# Sheet1.net
KiCad netlist of a schematic drawn in Altium Designer
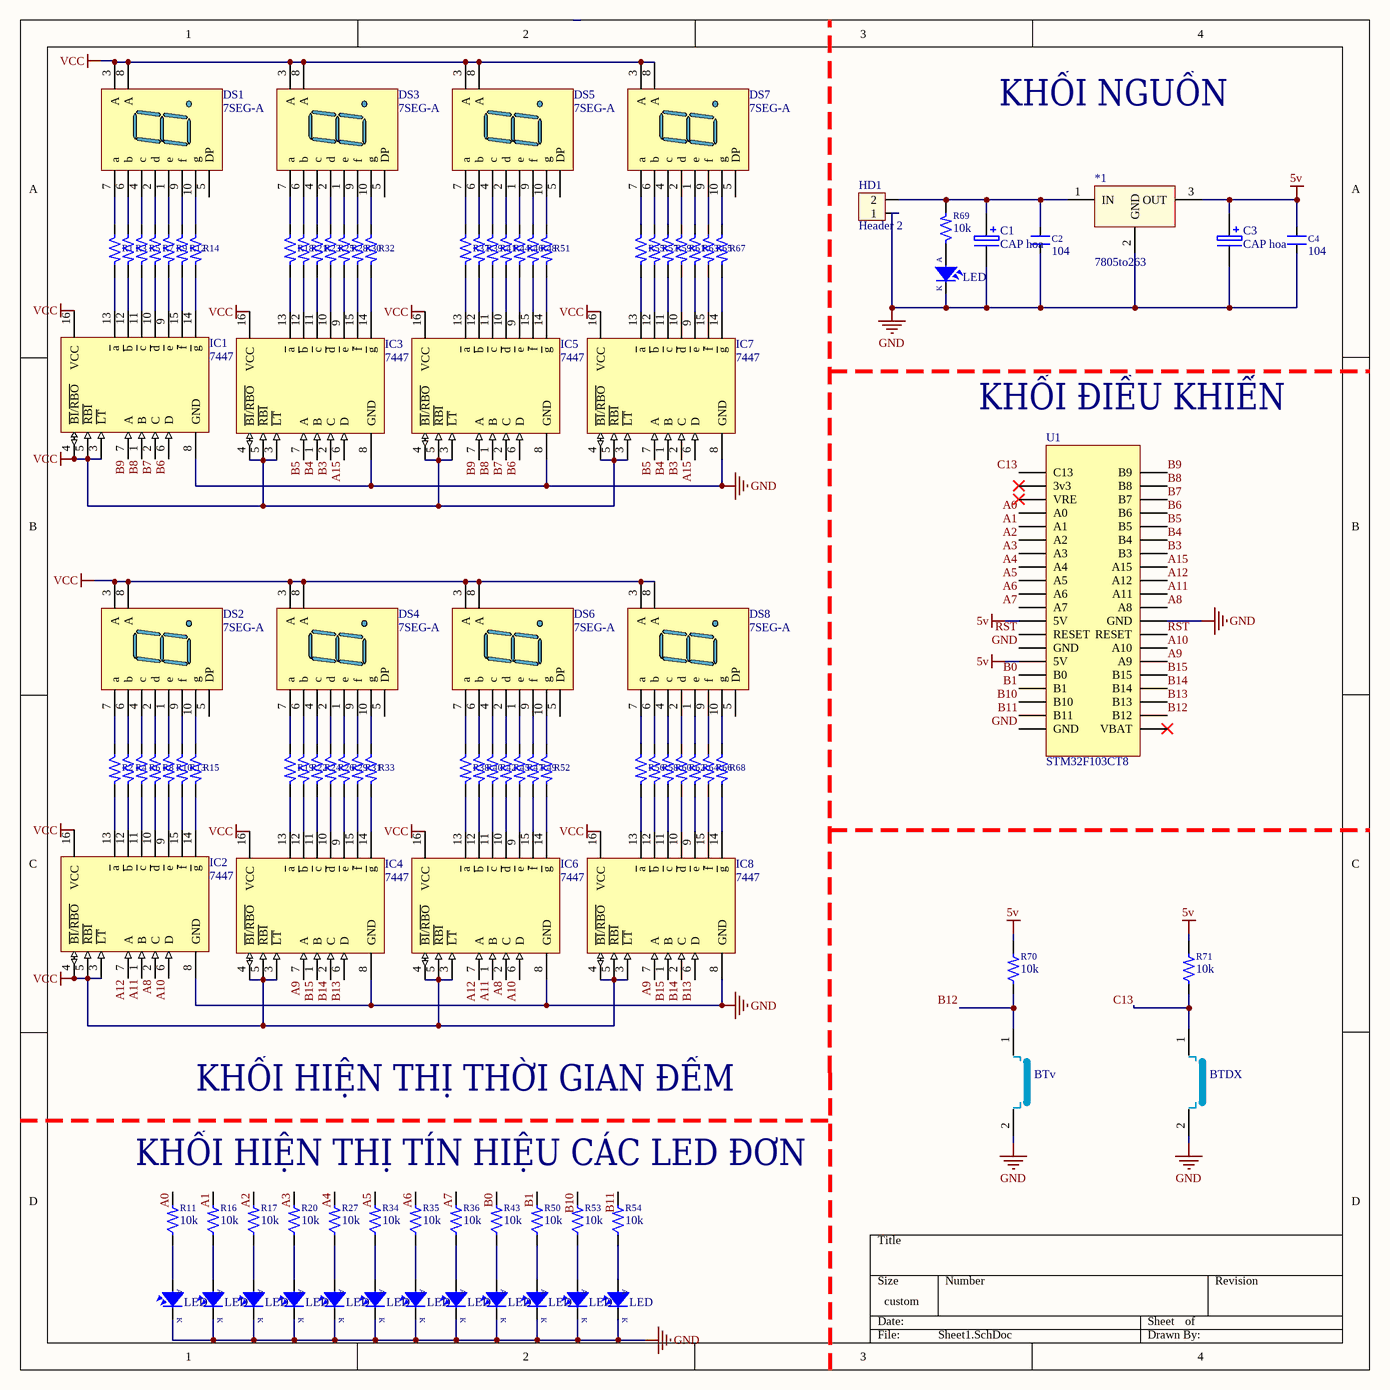
[diagram p0: Sheet1.SchDoc]

(export (version "E")
  (design (tool "Eeschema 10.0.6"))
  (components
    (comp (ref "*1") (value "7805to263") (footprint "7805") (libsource (lib "lananh_lib") (part "7805to263")))
    (comp (ref "BT1") (value "BTv") (footprint "SW4") (libsource (lib "CDT_Library") (part "BUTTON")))
    (comp (ref "BT2") (value "BTDX") (footprint "SW4") (libsource (lib "CDT_Library") (part "BUTTON")))
    (comp (ref "C1")
      (value "CAP hoa")
      (footprint "CP1/2")
      (description "Cap")
      (libsource (lib "CDT_Library") (part "CAP hoa"))
    )
    (comp (ref "C2")
      (value "104")
      (footprint "SM-CAP-0805")
      (fields (field (name "DESIGNED BY") "VanDungEvn"))
      (libsource (lib "CDT_Library") (part "CAP SMD"))
    )
    (comp (ref "C3")
      (value "CAP hoa")
      (footprint "CP1/2")
      (description "Cap")
      (libsource (lib "CDT_Library") (part "CAP hoa"))
    )
    (comp (ref "C4")
      (value "104")
      (footprint "SM-CAP-0805")
      (fields (field (name "DESIGNED BY") "VanDungEvn"))
      (libsource (lib "CDT_Library") (part "CAP SMD"))
    )
    (comp (ref "DS1")
      (value "7SEG-A")
      (footprint "LED7SEG")
      (description "14.2 mm General Purpose Blue 7-Segment Display: CA, RH DP, Gray Surface")
      (fields (field (name "PUBLISHER") "Altium Limited"))
      (libsource (lib "CDT_Library") (part "LED 7SEG-A"))
    )
    (comp (ref "DS2")
      (value "7SEG-A")
      (footprint "LED7SEG")
      (description "14.2 mm General Purpose Blue 7-Segment Display: CA, RH DP, Gray Surface")
      (fields (field (name "PUBLISHER") "Altium Limited"))
      (libsource (lib "CDT_Library") (part "LED 7SEG-A"))
    )
    (comp (ref "DS3")
      (value "7SEG-A")
      (footprint "LED7SEG")
      (description "14.2 mm General Purpose Blue 7-Segment Display: CA, RH DP, Gray Surface")
      (fields (field (name "PUBLISHER") "Altium Limited"))
      (libsource (lib "CDT_Library") (part "LED 7SEG-A"))
    )
    (comp (ref "DS4")
      (value "7SEG-A")
      (footprint "LED7SEG")
      (description "14.2 mm General Purpose Blue 7-Segment Display: CA, RH DP, Gray Surface")
      (fields (field (name "PUBLISHER") "Altium Limited"))
      (libsource (lib "CDT_Library") (part "LED 7SEG-A"))
    )
    (comp (ref "DS5")
      (value "7SEG-A")
      (footprint "LED7SEG")
      (description "14.2 mm General Purpose Blue 7-Segment Display: CA, RH DP, Gray Surface")
      (fields (field (name "PUBLISHER") "Altium Limited"))
      (libsource (lib "CDT_Library") (part "LED 7SEG-A"))
    )
    (comp (ref "DS6")
      (value "7SEG-A")
      (footprint "LED7SEG")
      (description "14.2 mm General Purpose Blue 7-Segment Display: CA, RH DP, Gray Surface")
      (fields (field (name "PUBLISHER") "Altium Limited"))
      (libsource (lib "CDT_Library") (part "LED 7SEG-A"))
    )
    (comp (ref "DS7")
      (value "7SEG-A")
      (footprint "LED7SEG")
      (description "14.2 mm General Purpose Blue 7-Segment Display: CA, RH DP, Gray Surface")
      (fields (field (name "PUBLISHER") "Altium Limited"))
      (libsource (lib "CDT_Library") (part "LED 7SEG-A"))
    )
    (comp (ref "DS8")
      (value "7SEG-A")
      (footprint "LED7SEG")
      (description "14.2 mm General Purpose Blue 7-Segment Display: CA, RH DP, Gray Surface")
      (fields (field (name "PUBLISHER") "Altium Limited"))
      (libsource (lib "CDT_Library") (part "LED 7SEG-A"))
    )
    (comp (ref "HD1")
      (value "Header 2")
      (footprint "HED2")
      (description "Header 2 (Green)")
      (libsource (lib "CDT_Library") (part "Header 2"))
    )
    (comp (ref "IC1")
      (value "7447")
      (footprint "ic74ls47")
      (description "BCD to 7-Segment Decoder/Driver")
      (libsource (lib "CDT_Library") (part "7447"))
    )
    (comp (ref "IC2")
      (value "7447")
      (footprint "ic74ls47")
      (description "BCD to 7-Segment Decoder/Driver")
      (libsource (lib "CDT_Library") (part "7447"))
    )
    (comp (ref "IC3")
      (value "7447")
      (footprint "ic74ls47")
      (description "BCD to 7-Segment Decoder/Driver")
      (libsource (lib "CDT_Library") (part "7447"))
    )
    (comp (ref "IC4")
      (value "7447")
      (footprint "ic74ls47")
      (description "BCD to 7-Segment Decoder/Driver")
      (libsource (lib "CDT_Library") (part "7447"))
    )
    (comp (ref "IC5")
      (value "7447")
      (footprint "ic74ls47")
      (description "BCD to 7-Segment Decoder/Driver")
      (libsource (lib "CDT_Library") (part "7447"))
    )
    (comp (ref "IC6")
      (value "7447")
      (footprint "ic74ls47")
      (description "BCD to 7-Segment Decoder/Driver")
      (libsource (lib "CDT_Library") (part "7447"))
    )
    (comp (ref "IC7")
      (value "7447")
      (footprint "ic74ls47")
      (description "BCD to 7-Segment Decoder/Driver")
      (libsource (lib "CDT_Library") (part "7447"))
    )
    (comp (ref "IC8")
      (value "7447")
      (footprint "ic74ls47")
      (description "BCD to 7-Segment Decoder/Driver")
      (libsource (lib "CDT_Library") (part "7447"))
    )
    (comp (ref "LED1")
      (value "LED")
      (footprint "LED-3")
      (description "LED Single colour Green and Red")
      (libsource (lib "CDT_Library") (part "LED"))
    )
    (comp (ref "LED2")
      (value "LED")
      (footprint "LED-3")
      (description "LED Single colour Green and Red")
      (libsource (lib "CDT_Library") (part "LED"))
    )
    (comp (ref "LED3")
      (value "LED")
      (footprint "LED-3")
      (description "LED Single colour Green and Red")
      (libsource (lib "CDT_Library") (part "LED"))
    )
    (comp (ref "LED4")
      (value "LED")
      (footprint "LED-3")
      (description "LED Single colour Green and Red")
      (libsource (lib "CDT_Library") (part "LED"))
    )
    (comp (ref "LED5")
      (value "LED")
      (footprint "LED-3")
      (description "LED Single colour Green and Red")
      (libsource (lib "CDT_Library") (part "LED"))
    )
    (comp (ref "LED6")
      (value "LED")
      (footprint "LED-3")
      (description "LED Single colour Green and Red")
      (libsource (lib "CDT_Library") (part "LED"))
    )
    (comp (ref "LED7")
      (value "LED")
      (footprint "LED-3")
      (description "LED Single colour Green and Red")
      (libsource (lib "CDT_Library") (part "LED"))
    )
    (comp (ref "LED8")
      (value "LED")
      (footprint "LED-3")
      (description "LED Single colour Green and Red")
      (libsource (lib "CDT_Library") (part "LED"))
    )
    (comp (ref "LED9")
      (value "LED")
      (footprint "LED-3")
      (description "LED Single colour Green and Red")
      (libsource (lib "CDT_Library") (part "LED"))
    )
    (comp (ref "LED10")
      (value "LED")
      (footprint "LED-3")
      (description "LED Single colour Green and Red")
      (libsource (lib "CDT_Library") (part "LED"))
    )
    (comp (ref "LED11")
      (value "LED")
      (footprint "LED-3")
      (description "LED Single colour Green and Red")
      (libsource (lib "CDT_Library") (part "LED"))
    )
    (comp (ref "LED12")
      (value "LED")
      (footprint "LED-3")
      (description "LED Single colour Green and Red")
      (libsource (lib "CDT_Library") (part "LED"))
    )
    (comp (ref "LED13")
      (value "LED")
      (footprint "LED-3")
      (description "LED Single colour Green and Red")
      (libsource (lib "CDT_Library") (part "LED"))
    )
    (comp (ref "R1")
      (value "10k")
      (footprint "Resistor SMD0603")
      (description "Res")
      (libsource (lib "CDT_Library") (part "Res SMD"))
    )
    (comp (ref "R2")
      (value "10k")
      (footprint "Resistor SMD0603")
      (description "Res")
      (libsource (lib "CDT_Library") (part "Res SMD"))
    )
    (comp (ref "R3")
      (value "10k")
      (footprint "Resistor SMD0603")
      (description "Res")
      (libsource (lib "CDT_Library") (part "Res SMD"))
    )
    (comp (ref "R4")
      (value "10k")
      (footprint "Resistor SMD0603")
      (description "Res")
      (libsource (lib "CDT_Library") (part "Res SMD"))
    )
    (comp (ref "R5")
      (value "10k")
      (footprint "Resistor SMD0603")
      (description "Res")
      (libsource (lib "CDT_Library") (part "Res SMD"))
    )
    (comp (ref "R6")
      (value "10k")
      (footprint "Resistor SMD0603")
      (description "Res")
      (libsource (lib "CDT_Library") (part "Res SMD"))
    )
    (comp (ref "R7")
      (value "10k")
      (footprint "Resistor SMD0603")
      (description "Res")
      (libsource (lib "CDT_Library") (part "Res SMD"))
    )
    (comp (ref "R8")
      (value "10k")
      (footprint "Resistor SMD0603")
      (description "Res")
      (libsource (lib "CDT_Library") (part "Res SMD"))
    )
    (comp (ref "R9")
      (value "10k")
      (footprint "Resistor SMD0603")
      (description "Res")
      (libsource (lib "CDT_Library") (part "Res SMD"))
    )
    (comp (ref "R10")
      (value "10k")
      (footprint "Resistor SMD0603")
      (description "Res")
      (libsource (lib "CDT_Library") (part "Res SMD"))
    )
    (comp (ref "R11")
      (value "10k")
      (footprint "Resistor SMD0603")
      (description "Res")
      (libsource (lib "CDT_Library") (part "Res SMD"))
    )
    (comp (ref "R12")
      (value "10k")
      (footprint "Resistor SMD0603")
      (description "Res")
      (libsource (lib "CDT_Library") (part "Res SMD"))
    )
    (comp (ref "R13")
      (value "10k")
      (footprint "Resistor SMD0603")
      (description "Res")
      (libsource (lib "CDT_Library") (part "Res SMD"))
    )
    (comp (ref "R14")
      (value "10k")
      (footprint "Resistor SMD0603")
      (description "Res")
      (libsource (lib "CDT_Library") (part "Res SMD"))
    )
    (comp (ref "R15")
      (value "10k")
      (footprint "Resistor SMD0603")
      (description "Res")
      (libsource (lib "CDT_Library") (part "Res SMD"))
    )
    (comp (ref "R16")
      (value "10k")
      (footprint "Resistor SMD0603")
      (description "Res")
      (libsource (lib "CDT_Library") (part "Res SMD"))
    )
    (comp (ref "R17")
      (value "10k")
      (footprint "Resistor SMD0603")
      (description "Res")
      (libsource (lib "CDT_Library") (part "Res SMD"))
    )
    (comp (ref "R18")
      (value "10k")
      (footprint "Resistor SMD0603")
      (description "Res")
      (libsource (lib "CDT_Library") (part "Res SMD"))
    )
    (comp (ref "R19")
      (value "10k")
      (footprint "Resistor SMD0603")
      (description "Res")
      (libsource (lib "CDT_Library") (part "Res SMD"))
    )
    (comp (ref "R20")
      (value "10k")
      (footprint "Resistor SMD0603")
      (description "Res")
      (libsource (lib "CDT_Library") (part "Res SMD"))
    )
    (comp (ref "R21")
      (value "10k")
      (footprint "Resistor SMD0603")
      (description "Res")
      (libsource (lib "CDT_Library") (part "Res SMD"))
    )
    (comp (ref "R22")
      (value "10k")
      (footprint "Resistor SMD0603")
      (description "Res")
      (libsource (lib "CDT_Library") (part "Res SMD"))
    )
    (comp (ref "R23")
      (value "10k")
      (footprint "Resistor SMD0603")
      (description "Res")
      (libsource (lib "CDT_Library") (part "Res SMD"))
    )
    (comp (ref "R24")
      (value "10k")
      (footprint "Resistor SMD0603")
      (description "Res")
      (libsource (lib "CDT_Library") (part "Res SMD"))
    )
    (comp (ref "R25")
      (value "10k")
      (footprint "Resistor SMD0603")
      (description "Res")
      (libsource (lib "CDT_Library") (part "Res SMD"))
    )
    (comp (ref "R26")
      (value "10k")
      (footprint "Resistor SMD0603")
      (description "Res")
      (libsource (lib "CDT_Library") (part "Res SMD"))
    )
    (comp (ref "R27")
      (value "10k")
      (footprint "Resistor SMD0603")
      (description "Res")
      (libsource (lib "CDT_Library") (part "Res SMD"))
    )
    (comp (ref "R28")
      (value "10k")
      (footprint "Resistor SMD0603")
      (description "Res")
      (libsource (lib "CDT_Library") (part "Res SMD"))
    )
    (comp (ref "R29")
      (value "10k")
      (footprint "Resistor SMD0603")
      (description "Res")
      (libsource (lib "CDT_Library") (part "Res SMD"))
    )
    (comp (ref "R30")
      (value "10k")
      (footprint "Resistor SMD0603")
      (description "Res")
      (libsource (lib "CDT_Library") (part "Res SMD"))
    )
    (comp (ref "R31")
      (value "10k")
      (footprint "Resistor SMD0603")
      (description "Res")
      (libsource (lib "CDT_Library") (part "Res SMD"))
    )
    (comp (ref "R32")
      (value "10k")
      (footprint "Resistor SMD0603")
      (description "Res")
      (libsource (lib "CDT_Library") (part "Res SMD"))
    )
    (comp (ref "R33")
      (value "10k")
      (footprint "Resistor SMD0603")
      (description "Res")
      (libsource (lib "CDT_Library") (part "Res SMD"))
    )
    (comp (ref "R34")
      (value "10k")
      (footprint "Resistor SMD0603")
      (description "Res")
      (libsource (lib "CDT_Library") (part "Res SMD"))
    )
    (comp (ref "R35")
      (value "10k")
      (footprint "Resistor SMD0603")
      (description "Res")
      (libsource (lib "CDT_Library") (part "Res SMD"))
    )
    (comp (ref "R36")
      (value "10k")
      (footprint "Resistor SMD0603")
      (description "Res")
      (libsource (lib "CDT_Library") (part "Res SMD"))
    )
    (comp (ref "R37")
      (value "10k")
      (footprint "Resistor SMD0603")
      (description "Res")
      (libsource (lib "CDT_Library") (part "Res SMD"))
    )
    (comp (ref "R38")
      (value "10k")
      (footprint "Resistor SMD0603")
      (description "Res")
      (libsource (lib "CDT_Library") (part "Res SMD"))
    )
    (comp (ref "R39")
      (value "10k")
      (footprint "Resistor SMD0603")
      (description "Res")
      (libsource (lib "CDT_Library") (part "Res SMD"))
    )
    (comp (ref "R40")
      (value "10k")
      (footprint "Resistor SMD0603")
      (description "Res")
      (libsource (lib "CDT_Library") (part "Res SMD"))
    )
    (comp (ref "R41")
      (value "10k")
      (footprint "Resistor SMD0603")
      (description "Res")
      (libsource (lib "CDT_Library") (part "Res SMD"))
    )
    (comp (ref "R42")
      (value "10k")
      (footprint "Resistor SMD0603")
      (description "Res")
      (libsource (lib "CDT_Library") (part "Res SMD"))
    )
    (comp (ref "R43")
      (value "10k")
      (footprint "Resistor SMD0603")
      (description "Res")
      (libsource (lib "CDT_Library") (part "Res SMD"))
    )
    (comp (ref "R44")
      (value "10k")
      (footprint "Resistor SMD0603")
      (description "Res")
      (libsource (lib "CDT_Library") (part "Res SMD"))
    )
    (comp (ref "R45")
      (value "10k")
      (footprint "Resistor SMD0603")
      (description "Res")
      (libsource (lib "CDT_Library") (part "Res SMD"))
    )
    (comp (ref "R46")
      (value "10k")
      (footprint "Resistor SMD0603")
      (description "Res")
      (libsource (lib "CDT_Library") (part "Res SMD"))
    )
    (comp (ref "R47")
      (value "10k")
      (footprint "Resistor SMD0603")
      (description "Res")
      (libsource (lib "CDT_Library") (part "Res SMD"))
    )
    (comp (ref "R48")
      (value "10k")
      (footprint "Resistor SMD0603")
      (description "Res")
      (libsource (lib "CDT_Library") (part "Res SMD"))
    )
    (comp (ref "R49")
      (value "10k")
      (footprint "Resistor SMD0603")
      (description "Res")
      (libsource (lib "CDT_Library") (part "Res SMD"))
    )
    (comp (ref "R50")
      (value "10k")
      (footprint "Resistor SMD0603")
      (description "Res")
      (libsource (lib "CDT_Library") (part "Res SMD"))
    )
    (comp (ref "R51")
      (value "10k")
      (footprint "Resistor SMD0603")
      (description "Res")
      (libsource (lib "CDT_Library") (part "Res SMD"))
    )
    (comp (ref "R52")
      (value "10k")
      (footprint "Resistor SMD0603")
      (description "Res")
      (libsource (lib "CDT_Library") (part "Res SMD"))
    )
    (comp (ref "R53")
      (value "10k")
      (footprint "Resistor SMD0603")
      (description "Res")
      (libsource (lib "CDT_Library") (part "Res SMD"))
    )
    (comp (ref "R54")
      (value "10k")
      (footprint "Resistor SMD0603")
      (description "Res")
      (libsource (lib "CDT_Library") (part "Res SMD"))
    )
    (comp (ref "R55")
      (value "10k")
      (footprint "Resistor SMD0603")
      (description "Res")
      (libsource (lib "CDT_Library") (part "Res SMD"))
    )
    (comp (ref "R56")
      (value "10k")
      (footprint "Resistor SMD0603")
      (description "Res")
      (libsource (lib "CDT_Library") (part "Res SMD"))
    )
    (comp (ref "R57")
      (value "10k")
      (footprint "Resistor SMD0603")
      (description "Res")
      (libsource (lib "CDT_Library") (part "Res SMD"))
    )
    (comp (ref "R58")
      (value "10k")
      (footprint "Resistor SMD0603")
      (description "Res")
      (libsource (lib "CDT_Library") (part "Res SMD"))
    )
    (comp (ref "R59")
      (value "10k")
      (footprint "Resistor SMD0603")
      (description "Res")
      (libsource (lib "CDT_Library") (part "Res SMD"))
    )
    (comp (ref "R60")
      (value "10k")
      (footprint "Resistor SMD0603")
      (description "Res")
      (libsource (lib "CDT_Library") (part "Res SMD"))
    )
    (comp (ref "R61")
      (value "10k")
      (footprint "Resistor SMD0603")
      (description "Res")
      (libsource (lib "CDT_Library") (part "Res SMD"))
    )
    (comp (ref "R62")
      (value "10k")
      (footprint "Resistor SMD0603")
      (description "Res")
      (libsource (lib "CDT_Library") (part "Res SMD"))
    )
    (comp (ref "R63")
      (value "10k")
      (footprint "Resistor SMD0603")
      (description "Res")
      (libsource (lib "CDT_Library") (part "Res SMD"))
    )
    (comp (ref "R64")
      (value "10k")
      (footprint "Resistor SMD0603")
      (description "Res")
      (libsource (lib "CDT_Library") (part "Res SMD"))
    )
    (comp (ref "R65")
      (value "10k")
      (footprint "Resistor SMD0603")
      (description "Res")
      (libsource (lib "CDT_Library") (part "Res SMD"))
    )
    (comp (ref "R66")
      (value "10k")
      (footprint "Resistor SMD0603")
      (description "Res")
      (libsource (lib "CDT_Library") (part "Res SMD"))
    )
    (comp (ref "R67")
      (value "10k")
      (footprint "Resistor SMD0603")
      (description "Res")
      (libsource (lib "CDT_Library") (part "Res SMD"))
    )
    (comp (ref "R68")
      (value "10k")
      (footprint "Resistor SMD0603")
      (description "Res")
      (libsource (lib "CDT_Library") (part "Res SMD"))
    )
    (comp (ref "R69")
      (value "10k")
      (footprint "Resistor SMD0603")
      (description "Res")
      (libsource (lib "CDT_Library") (part "Res SMD"))
    )
    (comp (ref "R70")
      (value "10k")
      (footprint "Resistor SMD0603")
      (description "Res")
      (libsource (lib "CDT_Library") (part "Res SMD"))
    )
    (comp (ref "R71")
      (value "10k")
      (footprint "Resistor SMD0603")
      (description "Res")
      (libsource (lib "CDT_Library") (part "Res SMD"))
    )
    (comp (ref "U1")
      (value "STM32F103CT8")
      (footprint "STM32F103CT6")
      (libsource (lib "Stm32f103ct6") (part "STM32F103CT8"))
    )
  )
  (nets
    (net (code "1") (name "/A0") (class "Default")
      (node (ref "R11") (pin "2") (pinfunction "2_2") (pintype "passive"))
      (node (ref "U1") (pin "4") (pinfunction "A0_4") (pintype "passive"))
    )
    (net (code "2") (name "/A1") (class "Default")
      (node (ref "R16") (pin "2") (pinfunction "2_2") (pintype "passive"))
      (node (ref "U1") (pin "5") (pinfunction "A1_5") (pintype "passive"))
    )
    (net (code "3") (name "/A2") (class "Default")
      (node (ref "R17") (pin "2") (pinfunction "2_2") (pintype "passive"))
      (node (ref "U1") (pin "6") (pinfunction "A2_6") (pintype "passive"))
    )
    (net (code "4") (name "/A3") (class "Default")
      (node (ref "R20") (pin "2") (pinfunction "2_2") (pintype "passive"))
      (node (ref "U1") (pin "7") (pinfunction "A3_7") (pintype "passive"))
    )
    (net (code "5") (name "/A4") (class "Default")
      (node (ref "R27") (pin "2") (pinfunction "2_2") (pintype "passive"))
      (node (ref "U1") (pin "8") (pinfunction "A4_8") (pintype "passive"))
    )
    (net (code "6") (name "/A5") (class "Default")
      (node (ref "R34") (pin "2") (pinfunction "2_2") (pintype "passive"))
      (node (ref "U1") (pin "9") (pinfunction "A5_9") (pintype "passive"))
    )
    (net (code "7") (name "/A6") (class "Default")
      (node (ref "R35") (pin "2") (pinfunction "2_2") (pintype "passive"))
      (node (ref "U1") (pin "10") (pinfunction "A6_10") (pintype "passive"))
    )
    (net (code "8") (name "/A7") (class "Default")
      (node (ref "R36") (pin "2") (pinfunction "2_2") (pintype "passive"))
      (node (ref "U1") (pin "11") (pinfunction "A7_11") (pintype "passive"))
    )
    (net (code "9") (name "/A8") (class "Default")
      (node (ref "IC2") (pin "2") (pinfunction "C_2") (pintype "input"))
      (node (ref "IC6") (pin "2") (pinfunction "C_2") (pintype "input"))
      (node (ref "U1") (pin "31") (pinfunction "A8_31") (pintype "passive"))
    )
    (net (code "10") (name "/A9") (class "Default")
      (node (ref "IC4") (pin "7") (pinfunction "A_7") (pintype "input"))
      (node (ref "IC8") (pin "7") (pinfunction "A_7") (pintype "input"))
      (node (ref "U1") (pin "35") (pinfunction "A9_35") (pintype "passive"))
    )
    (net (code "11") (name "/A10") (class "Default")
      (node (ref "IC2") (pin "6") (pinfunction "D_6") (pintype "input"))
      (node (ref "IC6") (pin "6") (pinfunction "D_6") (pintype "input"))
      (node (ref "U1") (pin "34") (pinfunction "A10_34") (pintype "passive"))
    )
    (net (code "12") (name "/A11") (class "Default")
      (node (ref "IC2") (pin "1") (pinfunction "B_1") (pintype "input"))
      (node (ref "IC6") (pin "1") (pinfunction "B_1") (pintype "input"))
      (node (ref "U1") (pin "30") (pinfunction "A11_30") (pintype "passive"))
    )
    (net (code "13") (name "/A12") (class "Default")
      (node (ref "IC2") (pin "7") (pinfunction "A_7") (pintype "input"))
      (node (ref "IC6") (pin "7") (pinfunction "A_7") (pintype "input"))
      (node (ref "U1") (pin "29") (pinfunction "A12_29") (pintype "passive"))
    )
    (net (code "14") (name "/A15") (class "Default")
      (node (ref "IC3") (pin "6") (pinfunction "D_6") (pintype "input"))
      (node (ref "IC7") (pin "6") (pinfunction "D_6") (pintype "input"))
      (node (ref "U1") (pin "28") (pinfunction "A15_28") (pintype "passive"))
    )
    (net (code "15") (name "/B0") (class "Default")
      (node (ref "R43") (pin "2") (pinfunction "2_2") (pintype "passive"))
      (node (ref "U1") (pin "16") (pinfunction "B0_16") (pintype "passive"))
    )
    (net (code "16") (name "/B1") (class "Default")
      (node (ref "R50") (pin "2") (pinfunction "2_2") (pintype "passive"))
      (node (ref "U1") (pin "17") (pinfunction "B1_17") (pintype "passive"))
    )
    (net (code "17") (name "/B3") (class "Default")
      (node (ref "IC3") (pin "2") (pinfunction "C_2") (pintype "input"))
      (node (ref "IC7") (pin "2") (pinfunction "C_2") (pintype "input"))
      (node (ref "U1") (pin "27") (pinfunction "B3_27") (pintype "passive"))
    )
    (net (code "18") (name "/B4") (class "Default")
      (node (ref "IC3") (pin "1") (pinfunction "B_1") (pintype "input"))
      (node (ref "IC7") (pin "1") (pinfunction "B_1") (pintype "input"))
      (node (ref "U1") (pin "26") (pinfunction "B4_26") (pintype "passive"))
    )
    (net (code "19") (name "/B5") (class "Default")
      (node (ref "IC3") (pin "7") (pinfunction "A_7") (pintype "input"))
      (node (ref "IC7") (pin "7") (pinfunction "A_7") (pintype "input"))
      (node (ref "U1") (pin "25") (pinfunction "B5_25") (pintype "passive"))
    )
    (net (code "20") (name "/B6") (class "Default")
      (node (ref "IC1") (pin "6") (pinfunction "D_6") (pintype "input"))
      (node (ref "IC5") (pin "6") (pinfunction "D_6") (pintype "input"))
      (node (ref "U1") (pin "24") (pinfunction "B6_24") (pintype "passive"))
    )
    (net (code "21") (name "/B7") (class "Default")
      (node (ref "IC1") (pin "2") (pinfunction "C_2") (pintype "input"))
      (node (ref "IC5") (pin "2") (pinfunction "C_2") (pintype "input"))
      (node (ref "U1") (pin "23") (pinfunction "B7_23") (pintype "power_in"))
    )
    (net (code "22") (name "/B8") (class "Default")
      (node (ref "IC1") (pin "1") (pinfunction "B_1") (pintype "input"))
      (node (ref "IC5") (pin "1") (pinfunction "B_1") (pintype "input"))
      (node (ref "U1") (pin "22") (pinfunction "B8_22") (pintype "passive"))
    )
    (net (code "23") (name "/B9") (class "Default")
      (node (ref "IC1") (pin "7") (pinfunction "A_7") (pintype "input"))
      (node (ref "IC5") (pin "7") (pinfunction "A_7") (pintype "input"))
      (node (ref "U1") (pin "21") (pinfunction "B9_21") (pintype "passive"))
    )
    (net (code "24") (name "/B10") (class "Default")
      (node (ref "R53") (pin "2") (pinfunction "2_2") (pintype "passive"))
      (node (ref "U1") (pin "18") (pinfunction "B10_18") (pintype "passive"))
    )
    (net (code "25") (name "/B11") (class "Default")
      (node (ref "R54") (pin "2") (pinfunction "2_2") (pintype "passive"))
      (node (ref "U1") (pin "19") (pinfunction "B11_19") (pintype "power_in"))
    )
    (net (code "26") (name "/B12") (class "Default")
      (node (ref "BT1") (pin "1") (pinfunction "1_1") (pintype "passive"))
      (node (ref "R70") (pin "1") (pinfunction "1_1") (pintype "passive"))
      (node (ref "U1") (pin "39") (pinfunction "B12_39") (pintype "passive"))
    )
    (net (code "27") (name "/B13") (class "Default")
      (node (ref "IC4") (pin "6") (pinfunction "D_6") (pintype "input"))
      (node (ref "IC8") (pin "6") (pinfunction "D_6") (pintype "input"))
      (node (ref "U1") (pin "38") (pinfunction "B13_38") (pintype "passive"))
    )
    (net (code "28") (name "/B14") (class "Default")
      (node (ref "IC4") (pin "2") (pinfunction "C_2") (pintype "input"))
      (node (ref "IC8") (pin "2") (pinfunction "C_2") (pintype "input"))
      (node (ref "U1") (pin "37") (pinfunction "B14_37") (pintype "passive"))
    )
    (net (code "29") (name "/B15") (class "Default")
      (node (ref "IC4") (pin "1") (pinfunction "B_1") (pintype "input"))
      (node (ref "IC8") (pin "1") (pinfunction "B_1") (pintype "input"))
      (node (ref "U1") (pin "36") (pinfunction "B15_36") (pintype "passive"))
    )
    (net (code "30") (name "/C13") (class "Default")
      (node (ref "BT2") (pin "1") (pinfunction "1_1") (pintype "passive"))
      (node (ref "R71") (pin "1") (pinfunction "1_1") (pintype "passive"))
      (node (ref "U1") (pin "1") (pinfunction "C13_1") (pintype "passive"))
    )
    (net (code "31") (name "/RST") (class "Default")
      (node (ref "U1") (pin "13") (pinfunction "RESET_13") (pintype "passive"))
      (node (ref "U1") (pin "33") (pinfunction "RESET_33") (pintype "passive"))
    )
    (net (code "32") (name "5v") (class "Default")
      (node (ref "*1") (pin "3") (pinfunction "OUT_3") (pintype "passive"))
      (node (ref "C3") (pin "1") (pintype "passive"))
      (node (ref "C4") (pin "2") (pinfunction "2_2") (pintype "passive"))
      (node (ref "R70") (pin "2") (pinfunction "2_2") (pintype "passive"))
      (node (ref "R71") (pin "2") (pinfunction "2_2") (pintype "passive"))
      (node (ref "U1") (pin "12") (pinfunction "5V_12") (pintype "power_in"))
      (node (ref "U1") (pin "15") (pinfunction "5V_15") (pintype "passive"))
    )
    (net (code "33") (name "GND") (class "Default")
      (node (ref "*1") (pin "2") (pinfunction "GND_2") (pintype "passive"))
      (node (ref "BT1") (pin "2") (pinfunction "2_2") (pintype "passive"))
      (node (ref "BT2") (pin "2") (pinfunction "2_2") (pintype "passive"))
      (node (ref "C1") (pin "2") (pintype "passive"))
      (node (ref "C2") (pin "1") (pinfunction "1_1") (pintype "passive"))
      (node (ref "C3") (pin "2") (pintype "passive"))
      (node (ref "C4") (pin "1") (pinfunction "1_1") (pintype "passive"))
      (node (ref "HD1") (pin "1") (pinfunction "1_1") (pintype "passive"))
      (node (ref "IC1") (pin "8") (pinfunction "GND_8") (pintype "power_in"))
      (node (ref "IC2") (pin "8") (pinfunction "GND_8") (pintype "power_in"))
      (node (ref "IC3") (pin "8") (pinfunction "GND_8") (pintype "power_in"))
      (node (ref "IC4") (pin "8") (pinfunction "GND_8") (pintype "power_in"))
      (node (ref "IC5") (pin "8") (pinfunction "GND_8") (pintype "power_in"))
      (node (ref "IC6") (pin "8") (pinfunction "GND_8") (pintype "power_in"))
      (node (ref "IC7") (pin "8") (pinfunction "GND_8") (pintype "power_in"))
      (node (ref "IC8") (pin "8") (pinfunction "GND_8") (pintype "power_in"))
      (node (ref "LED1") (pin "2") (pinfunction "K_2") (pintype "passive"))
      (node (ref "LED10") (pin "2") (pinfunction "K_2") (pintype "passive"))
      (node (ref "LED11") (pin "2") (pinfunction "K_2") (pintype "passive"))
      (node (ref "LED12") (pin "2") (pinfunction "K_2") (pintype "passive"))
      (node (ref "LED13") (pin "2") (pinfunction "K_2") (pintype "passive"))
      (node (ref "LED2") (pin "2") (pinfunction "K_2") (pintype "passive"))
      (node (ref "LED3") (pin "2") (pinfunction "K_2") (pintype "passive"))
      (node (ref "LED4") (pin "2") (pinfunction "K_2") (pintype "passive"))
      (node (ref "LED5") (pin "2") (pinfunction "K_2") (pintype "passive"))
      (node (ref "LED6") (pin "2") (pinfunction "K_2") (pintype "passive"))
      (node (ref "LED7") (pin "2") (pinfunction "K_2") (pintype "passive"))
      (node (ref "LED8") (pin "2") (pinfunction "K_2") (pintype "passive"))
      (node (ref "LED9") (pin "2") (pinfunction "K_2") (pintype "passive"))
      (node (ref "U1") (pin "14") (pinfunction "GND_14") (pintype "passive"))
      (node (ref "U1") (pin "20") (pinfunction "GND_20") (pintype "power_in"))
      (node (ref "U1") (pin "32") (pinfunction "GND_32") (pintype "passive"))
    )
    (net (code "34") (name "Net-(*1-IN)") (class "Default")
      (node (ref "*1") (pin "1") (pinfunction "IN_1") (pintype "passive"))
      (node (ref "C1") (pin "1") (pintype "passive"))
      (node (ref "C2") (pin "2") (pinfunction "2_2") (pintype "passive"))
      (node (ref "HD1") (pin "2") (pinfunction "2_2") (pintype "passive"))
      (node (ref "R69") (pin "2") (pinfunction "2_2") (pintype "passive"))
    )
    (net (code "35") (name "Net-(DS1-a)") (class "Default")
      (node (ref "DS1") (pin "7") (pinfunction "a_7") (pintype "passive"))
      (node (ref "R1") (pin "1") (pinfunction "1_1") (pintype "passive"))
    )
    (net (code "36") (name "Net-(DS1-b)") (class "Default")
      (node (ref "DS1") (pin "6") (pinfunction "b_6") (pintype "passive"))
      (node (ref "R3") (pin "1") (pinfunction "1_1") (pintype "passive"))
    )
    (net (code "37") (name "Net-(DS1-c)") (class "Default")
      (node (ref "DS1") (pin "4") (pinfunction "c_4") (pintype "passive"))
      (node (ref "R5") (pin "1") (pinfunction "1_1") (pintype "passive"))
    )
    (net (code "38") (name "Net-(DS1-d)") (class "Default")
      (node (ref "DS1") (pin "2") (pinfunction "d_2") (pintype "passive"))
      (node (ref "R7") (pin "1") (pinfunction "1_1") (pintype "passive"))
    )
    (net (code "39") (name "Net-(DS1-e)") (class "Default")
      (node (ref "DS1") (pin "1") (pinfunction "e_1") (pintype "passive"))
      (node (ref "R9") (pin "1") (pinfunction "1_1") (pintype "passive"))
    )
    (net (code "40") (name "Net-(DS1-f)") (class "Default")
      (node (ref "DS1") (pin "9") (pinfunction "f_9") (pintype "passive"))
      (node (ref "R12") (pin "1") (pinfunction "1_1") (pintype "passive"))
    )
    (net (code "41") (name "Net-(DS1-g)") (class "Default")
      (node (ref "DS1") (pin "10") (pinfunction "g_10") (pintype "passive"))
      (node (ref "R14") (pin "1") (pinfunction "1_1") (pintype "passive"))
    )
    (net (code "42") (name "Net-(DS2-a)") (class "Default")
      (node (ref "DS2") (pin "7") (pinfunction "a_7") (pintype "passive"))
      (node (ref "R2") (pin "1") (pinfunction "1_1") (pintype "passive"))
    )
    (net (code "43") (name "Net-(DS2-b)") (class "Default")
      (node (ref "DS2") (pin "6") (pinfunction "b_6") (pintype "passive"))
      (node (ref "R4") (pin "1") (pinfunction "1_1") (pintype "passive"))
    )
    (net (code "44") (name "Net-(DS2-c)") (class "Default")
      (node (ref "DS2") (pin "4") (pinfunction "c_4") (pintype "passive"))
      (node (ref "R6") (pin "1") (pinfunction "1_1") (pintype "passive"))
    )
    (net (code "45") (name "Net-(DS2-d)") (class "Default")
      (node (ref "DS2") (pin "2") (pinfunction "d_2") (pintype "passive"))
      (node (ref "R8") (pin "1") (pinfunction "1_1") (pintype "passive"))
    )
    (net (code "46") (name "Net-(DS2-e)") (class "Default")
      (node (ref "DS2") (pin "1") (pinfunction "e_1") (pintype "passive"))
      (node (ref "R10") (pin "1") (pinfunction "1_1") (pintype "passive"))
    )
    (net (code "47") (name "Net-(DS2-f)") (class "Default")
      (node (ref "DS2") (pin "9") (pinfunction "f_9") (pintype "passive"))
      (node (ref "R13") (pin "1") (pinfunction "1_1") (pintype "passive"))
    )
    (net (code "48") (name "Net-(DS2-g)") (class "Default")
      (node (ref "DS2") (pin "10") (pinfunction "g_10") (pintype "passive"))
      (node (ref "R15") (pin "1") (pinfunction "1_1") (pintype "passive"))
    )
    (net (code "49") (name "Net-(DS3-a)") (class "Default")
      (node (ref "DS3") (pin "7") (pinfunction "a_7") (pintype "passive"))
      (node (ref "R18") (pin "1") (pinfunction "1_1") (pintype "passive"))
    )
    (net (code "50") (name "Net-(DS3-b)") (class "Default")
      (node (ref "DS3") (pin "6") (pinfunction "b_6") (pintype "passive"))
      (node (ref "R21") (pin "1") (pinfunction "1_1") (pintype "passive"))
    )
    (net (code "51") (name "Net-(DS3-c)") (class "Default")
      (node (ref "DS3") (pin "4") (pinfunction "c_4") (pintype "passive"))
      (node (ref "R23") (pin "1") (pinfunction "1_1") (pintype "passive"))
    )
    (net (code "52") (name "Net-(DS3-d)") (class "Default")
      (node (ref "DS3") (pin "2") (pinfunction "d_2") (pintype "passive"))
      (node (ref "R25") (pin "1") (pinfunction "1_1") (pintype "passive"))
    )
    (net (code "53") (name "Net-(DS3-e)") (class "Default")
      (node (ref "DS3") (pin "1") (pinfunction "e_1") (pintype "passive"))
      (node (ref "R28") (pin "1") (pinfunction "1_1") (pintype "passive"))
    )
    (net (code "54") (name "Net-(DS3-f)") (class "Default")
      (node (ref "DS3") (pin "9") (pinfunction "f_9") (pintype "passive"))
      (node (ref "R30") (pin "1") (pinfunction "1_1") (pintype "passive"))
    )
    (net (code "55") (name "Net-(DS3-g)") (class "Default")
      (node (ref "DS3") (pin "10") (pinfunction "g_10") (pintype "passive"))
      (node (ref "R32") (pin "1") (pinfunction "1_1") (pintype "passive"))
    )
    (net (code "56") (name "Net-(DS4-a)") (class "Default")
      (node (ref "DS4") (pin "7") (pinfunction "a_7") (pintype "passive"))
      (node (ref "R19") (pin "1") (pinfunction "1_1") (pintype "passive"))
    )
    (net (code "57") (name "Net-(DS4-b)") (class "Default")
      (node (ref "DS4") (pin "6") (pinfunction "b_6") (pintype "passive"))
      (node (ref "R22") (pin "1") (pinfunction "1_1") (pintype "passive"))
    )
    (net (code "58") (name "Net-(DS4-c)") (class "Default")
      (node (ref "DS4") (pin "4") (pinfunction "c_4") (pintype "passive"))
      (node (ref "R24") (pin "1") (pinfunction "1_1") (pintype "passive"))
    )
    (net (code "59") (name "Net-(DS4-d)") (class "Default")
      (node (ref "DS4") (pin "2") (pinfunction "d_2") (pintype "passive"))
      (node (ref "R26") (pin "1") (pinfunction "1_1") (pintype "passive"))
    )
    (net (code "60") (name "Net-(DS4-e)") (class "Default")
      (node (ref "DS4") (pin "1") (pinfunction "e_1") (pintype "passive"))
      (node (ref "R29") (pin "1") (pinfunction "1_1") (pintype "passive"))
    )
    (net (code "61") (name "Net-(DS4-f)") (class "Default")
      (node (ref "DS4") (pin "9") (pinfunction "f_9") (pintype "passive"))
      (node (ref "R31") (pin "1") (pinfunction "1_1") (pintype "passive"))
    )
    (net (code "62") (name "Net-(DS4-g)") (class "Default")
      (node (ref "DS4") (pin "10") (pinfunction "g_10") (pintype "passive"))
      (node (ref "R33") (pin "1") (pinfunction "1_1") (pintype "passive"))
    )
    (net (code "63") (name "Net-(DS5-a)") (class "Default")
      (node (ref "DS5") (pin "7") (pinfunction "a_7") (pintype "passive"))
      (node (ref "R37") (pin "1") (pinfunction "1_1") (pintype "passive"))
    )
    (net (code "64") (name "Net-(DS5-b)") (class "Default")
      (node (ref "DS5") (pin "6") (pinfunction "b_6") (pintype "passive"))
      (node (ref "R39") (pin "1") (pinfunction "1_1") (pintype "passive"))
    )
    (net (code "65") (name "Net-(DS5-c)") (class "Default")
      (node (ref "DS5") (pin "4") (pinfunction "c_4") (pintype "passive"))
      (node (ref "R41") (pin "1") (pinfunction "1_1") (pintype "passive"))
    )
    (net (code "66") (name "Net-(DS5-d)") (class "Default")
      (node (ref "DS5") (pin "2") (pinfunction "d_2") (pintype "passive"))
      (node (ref "R44") (pin "1") (pinfunction "1_1") (pintype "passive"))
    )
    (net (code "67") (name "Net-(DS5-e)") (class "Default")
      (node (ref "DS5") (pin "1") (pinfunction "e_1") (pintype "passive"))
      (node (ref "R46") (pin "1") (pinfunction "1_1") (pintype "passive"))
    )
    (net (code "68") (name "Net-(DS5-f)") (class "Default")
      (node (ref "DS5") (pin "9") (pinfunction "f_9") (pintype "passive"))
      (node (ref "R48") (pin "1") (pinfunction "1_1") (pintype "passive"))
    )
    (net (code "69") (name "Net-(DS5-g)") (class "Default")
      (node (ref "DS5") (pin "10") (pinfunction "g_10") (pintype "passive"))
      (node (ref "R51") (pin "1") (pinfunction "1_1") (pintype "passive"))
    )
    (net (code "70") (name "Net-(DS6-a)") (class "Default")
      (node (ref "DS6") (pin "7") (pinfunction "a_7") (pintype "passive"))
      (node (ref "R38") (pin "1") (pinfunction "1_1") (pintype "passive"))
    )
    (net (code "71") (name "Net-(DS6-b)") (class "Default")
      (node (ref "DS6") (pin "6") (pinfunction "b_6") (pintype "passive"))
      (node (ref "R40") (pin "1") (pinfunction "1_1") (pintype "passive"))
    )
    (net (code "72") (name "Net-(DS6-c)") (class "Default")
      (node (ref "DS6") (pin "4") (pinfunction "c_4") (pintype "passive"))
      (node (ref "R42") (pin "1") (pinfunction "1_1") (pintype "passive"))
    )
    (net (code "73") (name "Net-(DS6-d)") (class "Default")
      (node (ref "DS6") (pin "2") (pinfunction "d_2") (pintype "passive"))
      (node (ref "R45") (pin "1") (pinfunction "1_1") (pintype "passive"))
    )
    (net (code "74") (name "Net-(DS6-e)") (class "Default")
      (node (ref "DS6") (pin "1") (pinfunction "e_1") (pintype "passive"))
      (node (ref "R47") (pin "1") (pinfunction "1_1") (pintype "passive"))
    )
    (net (code "75") (name "Net-(DS6-f)") (class "Default")
      (node (ref "DS6") (pin "9") (pinfunction "f_9") (pintype "passive"))
      (node (ref "R49") (pin "1") (pinfunction "1_1") (pintype "passive"))
    )
    (net (code "76") (name "Net-(DS6-g)") (class "Default")
      (node (ref "DS6") (pin "10") (pinfunction "g_10") (pintype "passive"))
      (node (ref "R52") (pin "1") (pinfunction "1_1") (pintype "passive"))
    )
    (net (code "77") (name "Net-(DS7-a)") (class "Default")
      (node (ref "DS7") (pin "7") (pinfunction "a_7") (pintype "passive"))
      (node (ref "R55") (pin "1") (pinfunction "1_1") (pintype "passive"))
    )
    (net (code "78") (name "Net-(DS7-b)") (class "Default")
      (node (ref "DS7") (pin "6") (pinfunction "b_6") (pintype "passive"))
      (node (ref "R57") (pin "1") (pinfunction "1_1") (pintype "passive"))
    )
    (net (code "79") (name "Net-(DS7-c)") (class "Default")
      (node (ref "DS7") (pin "4") (pinfunction "c_4") (pintype "passive"))
      (node (ref "R59") (pin "1") (pinfunction "1_1") (pintype "passive"))
    )
    (net (code "80") (name "Net-(DS7-d)") (class "Default")
      (node (ref "DS7") (pin "2") (pinfunction "d_2") (pintype "passive"))
      (node (ref "R61") (pin "1") (pinfunction "1_1") (pintype "passive"))
    )
    (net (code "81") (name "Net-(DS7-e)") (class "Default")
      (node (ref "DS7") (pin "1") (pinfunction "e_1") (pintype "passive"))
      (node (ref "R63") (pin "1") (pinfunction "1_1") (pintype "passive"))
    )
    (net (code "82") (name "Net-(DS7-f)") (class "Default")
      (node (ref "DS7") (pin "9") (pinfunction "f_9") (pintype "passive"))
      (node (ref "R65") (pin "1") (pinfunction "1_1") (pintype "passive"))
    )
    (net (code "83") (name "Net-(DS7-g)") (class "Default")
      (node (ref "DS7") (pin "10") (pinfunction "g_10") (pintype "passive"))
      (node (ref "R67") (pin "1") (pinfunction "1_1") (pintype "passive"))
    )
    (net (code "84") (name "Net-(DS8-a)") (class "Default")
      (node (ref "DS8") (pin "7") (pinfunction "a_7") (pintype "passive"))
      (node (ref "R56") (pin "1") (pinfunction "1_1") (pintype "passive"))
    )
    (net (code "85") (name "Net-(DS8-b)") (class "Default")
      (node (ref "DS8") (pin "6") (pinfunction "b_6") (pintype "passive"))
      (node (ref "R58") (pin "1") (pinfunction "1_1") (pintype "passive"))
    )
    (net (code "86") (name "Net-(DS8-c)") (class "Default")
      (node (ref "DS8") (pin "4") (pinfunction "c_4") (pintype "passive"))
      (node (ref "R60") (pin "1") (pinfunction "1_1") (pintype "passive"))
    )
    (net (code "87") (name "Net-(DS8-d)") (class "Default")
      (node (ref "DS8") (pin "2") (pinfunction "d_2") (pintype "passive"))
      (node (ref "R62") (pin "1") (pinfunction "1_1") (pintype "passive"))
    )
    (net (code "88") (name "Net-(DS8-e)") (class "Default")
      (node (ref "DS8") (pin "1") (pinfunction "e_1") (pintype "passive"))
      (node (ref "R64") (pin "1") (pinfunction "1_1") (pintype "passive"))
    )
    (net (code "89") (name "Net-(DS8-f)") (class "Default")
      (node (ref "DS8") (pin "9") (pinfunction "f_9") (pintype "passive"))
      (node (ref "R66") (pin "1") (pinfunction "1_1") (pintype "passive"))
    )
    (net (code "90") (name "Net-(DS8-g)") (class "Default")
      (node (ref "DS8") (pin "10") (pinfunction "g_10") (pintype "passive"))
      (node (ref "R68") (pin "1") (pinfunction "1_1") (pintype "passive"))
    )
    (net (code "91") (name "Net-(IC1-~{a})") (class "Default")
      (node (ref "IC1") (pin "13") (pinfunction "~{a}_13") (pintype "open_collector"))
      (node (ref "R1") (pin "2") (pinfunction "2_2") (pintype "passive"))
    )
    (net (code "92") (name "Net-(IC1-~{b})") (class "Default")
      (node (ref "IC1") (pin "12") (pinfunction "~{b}_12") (pintype "open_collector"))
      (node (ref "R3") (pin "2") (pinfunction "2_2") (pintype "passive"))
    )
    (net (code "93") (name "Net-(IC1-~{c})") (class "Default")
      (node (ref "IC1") (pin "11") (pinfunction "~{c}_11") (pintype "open_collector"))
      (node (ref "R5") (pin "2") (pinfunction "2_2") (pintype "passive"))
    )
    (net (code "94") (name "Net-(IC1-~{d})") (class "Default")
      (node (ref "IC1") (pin "10") (pinfunction "~{d}_10") (pintype "open_collector"))
      (node (ref "R7") (pin "2") (pinfunction "2_2") (pintype "passive"))
    )
    (net (code "95") (name "Net-(IC1-~{e})") (class "Default")
      (node (ref "IC1") (pin "9") (pinfunction "~{e}_9") (pintype "open_collector"))
      (node (ref "R9") (pin "2") (pinfunction "2_2") (pintype "passive"))
    )
    (net (code "96") (name "Net-(IC1-~{f})") (class "Default")
      (node (ref "IC1") (pin "15") (pinfunction "~{f}_15") (pintype "open_collector"))
      (node (ref "R12") (pin "2") (pinfunction "2_2") (pintype "passive"))
    )
    (net (code "97") (name "Net-(IC1-~{g})") (class "Default")
      (node (ref "IC1") (pin "14") (pinfunction "~{g}_14") (pintype "open_collector"))
      (node (ref "R14") (pin "2") (pinfunction "2_2") (pintype "passive"))
    )
    (net (code "98") (name "Net-(IC2-~{a})") (class "Default")
      (node (ref "IC2") (pin "13") (pinfunction "~{a}_13") (pintype "open_collector"))
      (node (ref "R2") (pin "2") (pinfunction "2_2") (pintype "passive"))
    )
    (net (code "99") (name "Net-(IC2-~{b})") (class "Default")
      (node (ref "IC2") (pin "12") (pinfunction "~{b}_12") (pintype "open_collector"))
      (node (ref "R4") (pin "2") (pinfunction "2_2") (pintype "passive"))
    )
    (net (code "100") (name "Net-(IC2-~{c})") (class "Default")
      (node (ref "IC2") (pin "11") (pinfunction "~{c}_11") (pintype "open_collector"))
      (node (ref "R6") (pin "2") (pinfunction "2_2") (pintype "passive"))
    )
    (net (code "101") (name "Net-(IC2-~{d})") (class "Default")
      (node (ref "IC2") (pin "10") (pinfunction "~{d}_10") (pintype "open_collector"))
      (node (ref "R8") (pin "2") (pinfunction "2_2") (pintype "passive"))
    )
    (net (code "102") (name "Net-(IC2-~{e})") (class "Default")
      (node (ref "IC2") (pin "9") (pinfunction "~{e}_9") (pintype "open_collector"))
      (node (ref "R10") (pin "2") (pinfunction "2_2") (pintype "passive"))
    )
    (net (code "103") (name "Net-(IC2-~{f})") (class "Default")
      (node (ref "IC2") (pin "15") (pinfunction "~{f}_15") (pintype "open_collector"))
      (node (ref "R13") (pin "2") (pinfunction "2_2") (pintype "passive"))
    )
    (net (code "104") (name "Net-(IC2-~{g})") (class "Default")
      (node (ref "IC2") (pin "14") (pinfunction "~{g}_14") (pintype "open_collector"))
      (node (ref "R15") (pin "2") (pinfunction "2_2") (pintype "passive"))
    )
    (net (code "105") (name "Net-(IC3-~{a})") (class "Default")
      (node (ref "IC3") (pin "13") (pinfunction "~{a}_13") (pintype "open_collector"))
      (node (ref "R18") (pin "2") (pinfunction "2_2") (pintype "passive"))
    )
    (net (code "106") (name "Net-(IC3-~{b})") (class "Default")
      (node (ref "IC3") (pin "12") (pinfunction "~{b}_12") (pintype "open_collector"))
      (node (ref "R21") (pin "2") (pinfunction "2_2") (pintype "passive"))
    )
    (net (code "107") (name "Net-(IC3-~{c})") (class "Default")
      (node (ref "IC3") (pin "11") (pinfunction "~{c}_11") (pintype "open_collector"))
      (node (ref "R23") (pin "2") (pinfunction "2_2") (pintype "passive"))
    )
    (net (code "108") (name "Net-(IC3-~{d})") (class "Default")
      (node (ref "IC3") (pin "10") (pinfunction "~{d}_10") (pintype "open_collector"))
      (node (ref "R25") (pin "2") (pinfunction "2_2") (pintype "passive"))
    )
    (net (code "109") (name "Net-(IC3-~{e})") (class "Default")
      (node (ref "IC3") (pin "9") (pinfunction "~{e}_9") (pintype "open_collector"))
      (node (ref "R28") (pin "2") (pinfunction "2_2") (pintype "passive"))
    )
    (net (code "110") (name "Net-(IC3-~{f})") (class "Default")
      (node (ref "IC3") (pin "15") (pinfunction "~{f}_15") (pintype "open_collector"))
      (node (ref "R30") (pin "2") (pinfunction "2_2") (pintype "passive"))
    )
    (net (code "111") (name "Net-(IC3-~{g})") (class "Default")
      (node (ref "IC3") (pin "14") (pinfunction "~{g}_14") (pintype "open_collector"))
      (node (ref "R32") (pin "2") (pinfunction "2_2") (pintype "passive"))
    )
    (net (code "112") (name "Net-(IC4-~{a})") (class "Default")
      (node (ref "IC4") (pin "13") (pinfunction "~{a}_13") (pintype "open_collector"))
      (node (ref "R19") (pin "2") (pinfunction "2_2") (pintype "passive"))
    )
    (net (code "113") (name "Net-(IC4-~{b})") (class "Default")
      (node (ref "IC4") (pin "12") (pinfunction "~{b}_12") (pintype "open_collector"))
      (node (ref "R22") (pin "2") (pinfunction "2_2") (pintype "passive"))
    )
    (net (code "114") (name "Net-(IC4-~{c})") (class "Default")
      (node (ref "IC4") (pin "11") (pinfunction "~{c}_11") (pintype "open_collector"))
      (node (ref "R24") (pin "2") (pinfunction "2_2") (pintype "passive"))
    )
    (net (code "115") (name "Net-(IC4-~{d})") (class "Default")
      (node (ref "IC4") (pin "10") (pinfunction "~{d}_10") (pintype "open_collector"))
      (node (ref "R26") (pin "2") (pinfunction "2_2") (pintype "passive"))
    )
    (net (code "116") (name "Net-(IC4-~{e})") (class "Default")
      (node (ref "IC4") (pin "9") (pinfunction "~{e}_9") (pintype "open_collector"))
      (node (ref "R29") (pin "2") (pinfunction "2_2") (pintype "passive"))
    )
    (net (code "117") (name "Net-(IC4-~{f})") (class "Default")
      (node (ref "IC4") (pin "15") (pinfunction "~{f}_15") (pintype "open_collector"))
      (node (ref "R31") (pin "2") (pinfunction "2_2") (pintype "passive"))
    )
    (net (code "118") (name "Net-(IC4-~{g})") (class "Default")
      (node (ref "IC4") (pin "14") (pinfunction "~{g}_14") (pintype "open_collector"))
      (node (ref "R33") (pin "2") (pinfunction "2_2") (pintype "passive"))
    )
    (net (code "119") (name "Net-(IC5-~{a})") (class "Default")
      (node (ref "IC5") (pin "13") (pinfunction "~{a}_13") (pintype "open_collector"))
      (node (ref "R37") (pin "2") (pinfunction "2_2") (pintype "passive"))
    )
    (net (code "120") (name "Net-(IC5-~{b})") (class "Default")
      (node (ref "IC5") (pin "12") (pinfunction "~{b}_12") (pintype "open_collector"))
      (node (ref "R39") (pin "2") (pinfunction "2_2") (pintype "passive"))
    )
    (net (code "121") (name "Net-(IC5-~{c})") (class "Default")
      (node (ref "IC5") (pin "11") (pinfunction "~{c}_11") (pintype "open_collector"))
      (node (ref "R41") (pin "2") (pinfunction "2_2") (pintype "passive"))
    )
    (net (code "122") (name "Net-(IC5-~{d})") (class "Default")
      (node (ref "IC5") (pin "10") (pinfunction "~{d}_10") (pintype "open_collector"))
      (node (ref "R44") (pin "2") (pinfunction "2_2") (pintype "passive"))
    )
    (net (code "123") (name "Net-(IC5-~{e})") (class "Default")
      (node (ref "IC5") (pin "9") (pinfunction "~{e}_9") (pintype "open_collector"))
      (node (ref "R46") (pin "2") (pinfunction "2_2") (pintype "passive"))
    )
    (net (code "124") (name "Net-(IC5-~{f})") (class "Default")
      (node (ref "IC5") (pin "15") (pinfunction "~{f}_15") (pintype "open_collector"))
      (node (ref "R48") (pin "2") (pinfunction "2_2") (pintype "passive"))
    )
    (net (code "125") (name "Net-(IC5-~{g})") (class "Default")
      (node (ref "IC5") (pin "14") (pinfunction "~{g}_14") (pintype "open_collector"))
      (node (ref "R51") (pin "2") (pinfunction "2_2") (pintype "passive"))
    )
    (net (code "126") (name "Net-(IC6-~{a})") (class "Default")
      (node (ref "IC6") (pin "13") (pinfunction "~{a}_13") (pintype "open_collector"))
      (node (ref "R38") (pin "2") (pinfunction "2_2") (pintype "passive"))
    )
    (net (code "127") (name "Net-(IC6-~{b})") (class "Default")
      (node (ref "IC6") (pin "12") (pinfunction "~{b}_12") (pintype "open_collector"))
      (node (ref "R40") (pin "2") (pinfunction "2_2") (pintype "passive"))
    )
    (net (code "128") (name "Net-(IC6-~{c})") (class "Default")
      (node (ref "IC6") (pin "11") (pinfunction "~{c}_11") (pintype "open_collector"))
      (node (ref "R42") (pin "2") (pinfunction "2_2") (pintype "passive"))
    )
    (net (code "129") (name "Net-(IC6-~{d})") (class "Default")
      (node (ref "IC6") (pin "10") (pinfunction "~{d}_10") (pintype "open_collector"))
      (node (ref "R45") (pin "2") (pinfunction "2_2") (pintype "passive"))
    )
    (net (code "130") (name "Net-(IC6-~{e})") (class "Default")
      (node (ref "IC6") (pin "9") (pinfunction "~{e}_9") (pintype "open_collector"))
      (node (ref "R47") (pin "2") (pinfunction "2_2") (pintype "passive"))
    )
    (net (code "131") (name "Net-(IC6-~{f})") (class "Default")
      (node (ref "IC6") (pin "15") (pinfunction "~{f}_15") (pintype "open_collector"))
      (node (ref "R49") (pin "2") (pinfunction "2_2") (pintype "passive"))
    )
    (net (code "132") (name "Net-(IC6-~{g})") (class "Default")
      (node (ref "IC6") (pin "14") (pinfunction "~{g}_14") (pintype "open_collector"))
      (node (ref "R52") (pin "2") (pinfunction "2_2") (pintype "passive"))
    )
    (net (code "133") (name "Net-(IC7-~{a})") (class "Default")
      (node (ref "IC7") (pin "13") (pinfunction "~{a}_13") (pintype "open_collector"))
      (node (ref "R55") (pin "2") (pinfunction "2_2") (pintype "passive"))
    )
    (net (code "134") (name "Net-(IC7-~{b})") (class "Default")
      (node (ref "IC7") (pin "12") (pinfunction "~{b}_12") (pintype "open_collector"))
      (node (ref "R57") (pin "2") (pinfunction "2_2") (pintype "passive"))
    )
    (net (code "135") (name "Net-(IC7-~{c})") (class "Default")
      (node (ref "IC7") (pin "11") (pinfunction "~{c}_11") (pintype "open_collector"))
      (node (ref "R59") (pin "2") (pinfunction "2_2") (pintype "passive"))
    )
    (net (code "136") (name "Net-(IC7-~{d})") (class "Default")
      (node (ref "IC7") (pin "10") (pinfunction "~{d}_10") (pintype "open_collector"))
      (node (ref "R61") (pin "2") (pinfunction "2_2") (pintype "passive"))
    )
    (net (code "137") (name "Net-(IC7-~{e})") (class "Default")
      (node (ref "IC7") (pin "9") (pinfunction "~{e}_9") (pintype "open_collector"))
      (node (ref "R63") (pin "2") (pinfunction "2_2") (pintype "passive"))
    )
    (net (code "138") (name "Net-(IC7-~{f})") (class "Default")
      (node (ref "IC7") (pin "15") (pinfunction "~{f}_15") (pintype "open_collector"))
      (node (ref "R65") (pin "2") (pinfunction "2_2") (pintype "passive"))
    )
    (net (code "139") (name "Net-(IC7-~{g})") (class "Default")
      (node (ref "IC7") (pin "14") (pinfunction "~{g}_14") (pintype "open_collector"))
      (node (ref "R67") (pin "2") (pinfunction "2_2") (pintype "passive"))
    )
    (net (code "140") (name "Net-(IC8-~{a})") (class "Default")
      (node (ref "IC8") (pin "13") (pinfunction "~{a}_13") (pintype "open_collector"))
      (node (ref "R56") (pin "2") (pinfunction "2_2") (pintype "passive"))
    )
    (net (code "141") (name "Net-(IC8-~{b})") (class "Default")
      (node (ref "IC8") (pin "12") (pinfunction "~{b}_12") (pintype "open_collector"))
      (node (ref "R58") (pin "2") (pinfunction "2_2") (pintype "passive"))
    )
    (net (code "142") (name "Net-(IC8-~{c})") (class "Default")
      (node (ref "IC8") (pin "11") (pinfunction "~{c}_11") (pintype "open_collector"))
      (node (ref "R60") (pin "2") (pinfunction "2_2") (pintype "passive"))
    )
    (net (code "143") (name "Net-(IC8-~{d})") (class "Default")
      (node (ref "IC8") (pin "10") (pinfunction "~{d}_10") (pintype "open_collector"))
      (node (ref "R62") (pin "2") (pinfunction "2_2") (pintype "passive"))
    )
    (net (code "144") (name "Net-(IC8-~{e})") (class "Default")
      (node (ref "IC8") (pin "9") (pinfunction "~{e}_9") (pintype "open_collector"))
      (node (ref "R64") (pin "2") (pinfunction "2_2") (pintype "passive"))
    )
    (net (code "145") (name "Net-(IC8-~{f})") (class "Default")
      (node (ref "IC8") (pin "15") (pinfunction "~{f}_15") (pintype "open_collector"))
      (node (ref "R66") (pin "2") (pinfunction "2_2") (pintype "passive"))
    )
    (net (code "146") (name "Net-(IC8-~{g})") (class "Default")
      (node (ref "IC8") (pin "14") (pinfunction "~{g}_14") (pintype "open_collector"))
      (node (ref "R68") (pin "2") (pinfunction "2_2") (pintype "passive"))
    )
    (net (code "147") (name "Net-(LED1-A)") (class "Default")
      (node (ref "LED1") (pin "1") (pinfunction "A_1") (pintype "passive"))
      (node (ref "R11") (pin "1") (pinfunction "1_1") (pintype "passive"))
    )
    (net (code "148") (name "Net-(LED2-A)") (class "Default")
      (node (ref "LED2") (pin "1") (pinfunction "A_1") (pintype "passive"))
      (node (ref "R16") (pin "1") (pinfunction "1_1") (pintype "passive"))
    )
    (net (code "149") (name "Net-(LED3-A)") (class "Default")
      (node (ref "LED3") (pin "1") (pinfunction "A_1") (pintype "passive"))
      (node (ref "R17") (pin "1") (pinfunction "1_1") (pintype "passive"))
    )
    (net (code "150") (name "Net-(LED4-A)") (class "Default")
      (node (ref "LED4") (pin "1") (pinfunction "A_1") (pintype "passive"))
      (node (ref "R20") (pin "1") (pinfunction "1_1") (pintype "passive"))
    )
    (net (code "151") (name "Net-(LED5-A)") (class "Default")
      (node (ref "LED5") (pin "1") (pinfunction "A_1") (pintype "passive"))
      (node (ref "R27") (pin "1") (pinfunction "1_1") (pintype "passive"))
    )
    (net (code "152") (name "Net-(LED6-A)") (class "Default")
      (node (ref "LED6") (pin "1") (pinfunction "A_1") (pintype "passive"))
      (node (ref "R34") (pin "1") (pinfunction "1_1") (pintype "passive"))
    )
    (net (code "153") (name "Net-(LED7-A)") (class "Default")
      (node (ref "LED7") (pin "1") (pinfunction "A_1") (pintype "passive"))
      (node (ref "R35") (pin "1") (pinfunction "1_1") (pintype "passive"))
    )
    (net (code "154") (name "Net-(LED8-A)") (class "Default")
      (node (ref "LED8") (pin "1") (pinfunction "A_1") (pintype "passive"))
      (node (ref "R36") (pin "1") (pinfunction "1_1") (pintype "passive"))
    )
    (net (code "155") (name "Net-(LED9-A)") (class "Default")
      (node (ref "LED9") (pin "1") (pinfunction "A_1") (pintype "passive"))
      (node (ref "R43") (pin "1") (pinfunction "1_1") (pintype "passive"))
    )
    (net (code "156") (name "Net-(LED10-A)") (class "Default")
      (node (ref "LED10") (pin "1") (pinfunction "A_1") (pintype "passive"))
      (node (ref "R50") (pin "1") (pinfunction "1_1") (pintype "passive"))
    )
    (net (code "157") (name "Net-(LED11-A)") (class "Default")
      (node (ref "LED11") (pin "1") (pinfunction "A_1") (pintype "passive"))
      (node (ref "R53") (pin "1") (pinfunction "1_1") (pintype "passive"))
    )
    (net (code "158") (name "Net-(LED12-A)") (class "Default")
      (node (ref "LED12") (pin "1") (pinfunction "A_1") (pintype "passive"))
      (node (ref "R54") (pin "1") (pinfunction "1_1") (pintype "passive"))
    )
    (net (code "159") (name "Net-(LED13-A)") (class "Default")
      (node (ref "LED13") (pin "1") (pinfunction "A_1") (pintype "passive"))
      (node (ref "R69") (pin "1") (pinfunction "1_1") (pintype "passive"))
    )
    (net (code "160") (name "VCC") (class "Default")
      (node (ref "DS1") (pin "3") (pinfunction "A_3") (pintype "passive"))
      (node (ref "DS1") (pin "8") (pinfunction "A_8") (pintype "passive"))
      (node (ref "DS2") (pin "3") (pinfunction "A_3") (pintype "passive"))
      (node (ref "DS2") (pin "8") (pinfunction "A_8") (pintype "passive"))
      (node (ref "DS3") (pin "3") (pinfunction "A_3") (pintype "passive"))
      (node (ref "DS3") (pin "8") (pinfunction "A_8") (pintype "passive"))
      (node (ref "DS4") (pin "3") (pinfunction "A_3") (pintype "passive"))
      (node (ref "DS4") (pin "8") (pinfunction "A_8") (pintype "passive"))
      (node (ref "DS5") (pin "3") (pinfunction "A_3") (pintype "passive"))
      (node (ref "DS5") (pin "8") (pinfunction "A_8") (pintype "passive"))
      (node (ref "DS6") (pin "3") (pinfunction "A_3") (pintype "passive"))
      (node (ref "DS6") (pin "8") (pinfunction "A_8") (pintype "passive"))
      (node (ref "DS7") (pin "3") (pinfunction "A_3") (pintype "passive"))
      (node (ref "DS7") (pin "8") (pinfunction "A_8") (pintype "passive"))
      (node (ref "DS8") (pin "3") (pinfunction "A_3") (pintype "passive"))
      (node (ref "DS8") (pin "8") (pinfunction "A_8") (pintype "passive"))
      (node (ref "IC1") (pin "16") (pinfunction "VCC_16") (pintype "power_in"))
      (node (ref "IC1") (pin "3") (pinfunction "~{LT}_3") (pintype "input"))
      (node (ref "IC1") (pin "4") (pinfunction "~{BI}/~{RBO}_4") (pintype "bidirectional"))
      (node (ref "IC1") (pin "5") (pinfunction "~{RBI}_5") (pintype "input"))
      (node (ref "IC2") (pin "16") (pinfunction "VCC_16") (pintype "power_in"))
      (node (ref "IC2") (pin "3") (pinfunction "~{LT}_3") (pintype "input"))
      (node (ref "IC2") (pin "4") (pinfunction "~{BI}/~{RBO}_4") (pintype "bidirectional"))
      (node (ref "IC2") (pin "5") (pinfunction "~{RBI}_5") (pintype "input"))
      (node (ref "IC3") (pin "16") (pinfunction "VCC_16") (pintype "power_in"))
      (node (ref "IC3") (pin "3") (pinfunction "~{LT}_3") (pintype "input"))
      (node (ref "IC3") (pin "4") (pinfunction "~{BI}/~{RBO}_4") (pintype "bidirectional"))
      (node (ref "IC3") (pin "5") (pinfunction "~{RBI}_5") (pintype "input"))
      (node (ref "IC4") (pin "16") (pinfunction "VCC_16") (pintype "power_in"))
      (node (ref "IC4") (pin "3") (pinfunction "~{LT}_3") (pintype "input"))
      (node (ref "IC4") (pin "4") (pinfunction "~{BI}/~{RBO}_4") (pintype "bidirectional"))
      (node (ref "IC4") (pin "5") (pinfunction "~{RBI}_5") (pintype "input"))
      (node (ref "IC5") (pin "16") (pinfunction "VCC_16") (pintype "power_in"))
      (node (ref "IC5") (pin "3") (pinfunction "~{LT}_3") (pintype "input"))
      (node (ref "IC5") (pin "4") (pinfunction "~{BI}/~{RBO}_4") (pintype "bidirectional"))
      (node (ref "IC5") (pin "5") (pinfunction "~{RBI}_5") (pintype "input"))
      (node (ref "IC6") (pin "16") (pinfunction "VCC_16") (pintype "power_in"))
      (node (ref "IC6") (pin "3") (pinfunction "~{LT}_3") (pintype "input"))
      (node (ref "IC6") (pin "4") (pinfunction "~{BI}/~{RBO}_4") (pintype "bidirectional"))
      (node (ref "IC6") (pin "5") (pinfunction "~{RBI}_5") (pintype "input"))
      (node (ref "IC7") (pin "16") (pinfunction "VCC_16") (pintype "power_in"))
      (node (ref "IC7") (pin "3") (pinfunction "~{LT}_3") (pintype "input"))
      (node (ref "IC7") (pin "4") (pinfunction "~{BI}/~{RBO}_4") (pintype "bidirectional"))
      (node (ref "IC7") (pin "5") (pinfunction "~{RBI}_5") (pintype "input"))
      (node (ref "IC8") (pin "16") (pinfunction "VCC_16") (pintype "power_in"))
      (node (ref "IC8") (pin "3") (pinfunction "~{LT}_3") (pintype "input"))
      (node (ref "IC8") (pin "4") (pinfunction "~{BI}/~{RBO}_4") (pintype "bidirectional"))
      (node (ref "IC8") (pin "5") (pinfunction "~{RBI}_5") (pintype "input"))
    )
    (net (code "161") (name "unconnected-(DS1-DP-Pad5)") (class "Default")
      (node (ref "DS1") (pin "5") (pinfunction "DP_5") (pintype "passive"))
    )
    (net (code "162") (name "unconnected-(DS2-DP-Pad5)") (class "Default")
      (node (ref "DS2") (pin "5") (pinfunction "DP_5") (pintype "passive"))
    )
    (net (code "163") (name "unconnected-(DS3-DP-Pad5)") (class "Default")
      (node (ref "DS3") (pin "5") (pinfunction "DP_5") (pintype "passive"))
    )
    (net (code "164") (name "unconnected-(DS4-DP-Pad5)") (class "Default")
      (node (ref "DS4") (pin "5") (pinfunction "DP_5") (pintype "passive"))
    )
    (net (code "165") (name "unconnected-(DS5-DP-Pad5)") (class "Default")
      (node (ref "DS5") (pin "5") (pinfunction "DP_5") (pintype "passive"))
    )
    (net (code "166") (name "unconnected-(DS6-DP-Pad5)") (class "Default")
      (node (ref "DS6") (pin "5") (pinfunction "DP_5") (pintype "passive"))
    )
    (net (code "167") (name "unconnected-(DS7-DP-Pad5)") (class "Default")
      (node (ref "DS7") (pin "5") (pinfunction "DP_5") (pintype "passive"))
    )
    (net (code "168") (name "unconnected-(DS8-DP-Pad5)") (class "Default")
      (node (ref "DS8") (pin "5") (pinfunction "DP_5") (pintype "passive"))
    )
    (net (code "169") (name "unconnected-(U1-3v3-Pad2)") (class "Default")
      (node (ref "U1") (pin "2") (pinfunction "3v3_2") (pintype "passive+no_connect"))
    )
    (net (code "170") (name "unconnected-(U1-VBAT-Pad40)") (class "Default")
      (node (ref "U1") (pin "40") (pinfunction "VBAT_40") (pintype "passive+no_connect"))
    )
    (net (code "171") (name "unconnected-(U1-VRE-Pad3)") (class "Default")
      (node (ref "U1") (pin "3") (pinfunction "VRE_3") (pintype "passive+no_connect"))
    )
  )
)
